# core.net
KiCad netlist of a schematic drawn in EAGLE
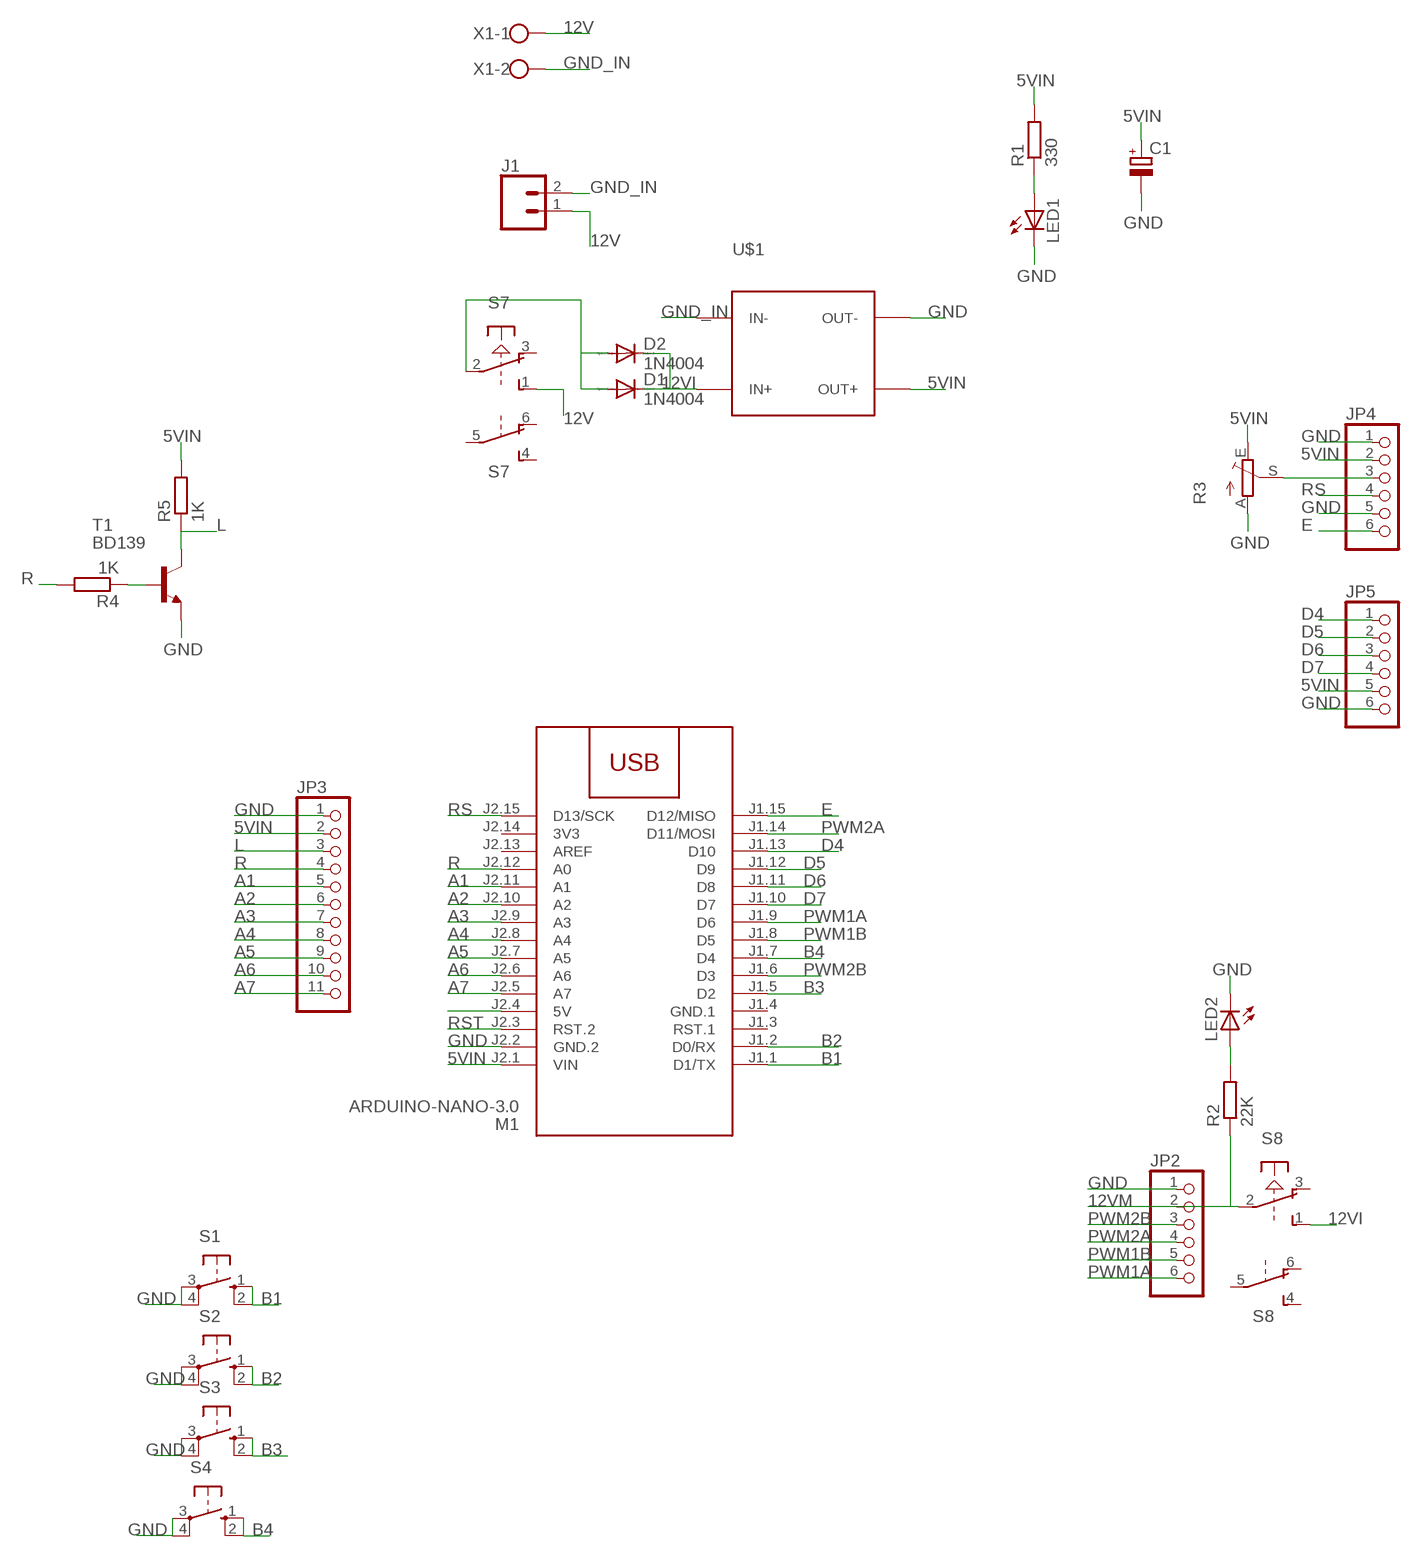
[diagram p0: schematic, sheet 1]

(export (version "E")
  (design (tool "Eeschema 10.0.6"))
  (components
    (comp (ref "C1")
      (value "CPOL-EUE2.5-6")
      (footprint "eagle-import:E2,5-6")
      (libsource (lib "eagle-import") (part "CPOL-EUE2.5-6"))
    )
    (comp (ref "D1")
      (value "1N4004")
      (footprint "eagle-import:DO41-10")
      (libsource (lib "eagle-import") (part "1N4004"))
    )
    (comp (ref "D2")
      (value "1N4004")
      (footprint "eagle-import:DO41-10")
      (libsource (lib "eagle-import") (part "1N4004"))
    )
    (comp (ref "J1")
      (value "CONN_02POLAR")
      (footprint "eagle-import:MOLEX-1X2")
      (libsource (lib "eagle-import") (part "CONN_02POLAR"))
    )
    (comp (ref "JP2")
      (value "PINHD-1X6")
      (footprint "eagle-import:1X06")
      (libsource (lib "eagle-import") (part "PINHD-1X6"))
    )
    (comp (ref "JP3")
      (value "PINHD-1X11")
      (footprint "eagle-import:1X11")
      (libsource (lib "eagle-import") (part "PINHD-1X11"))
    )
    (comp (ref "JP4")
      (value "PINHD-1X6")
      (footprint "eagle-import:1X06")
      (libsource (lib "eagle-import") (part "PINHD-1X6"))
    )
    (comp (ref "JP5")
      (value "PINHD-1X6")
      (footprint "eagle-import:1X06")
      (libsource (lib "eagle-import") (part "PINHD-1X6"))
    )
    (comp (ref "LED1")
      (value "LED3MM")
      (footprint "eagle-import:LED3MM")
      (libsource (lib "eagle-import") (part "LED3MM"))
    )
    (comp (ref "LED2")
      (value "LED3MM")
      (footprint "eagle-import:LED3MM")
      (libsource (lib "eagle-import") (part "LED3MM"))
    )
    (comp (ref "M1")
      (value "ARDUINO-NANO-3.0")
      (footprint "eagle-import:ARDUINO-NANO-3.0")
      (libsource (lib "eagle-import") (part "ARDUINO-NANO-3.0"))
    )
    (comp (ref "R1")
      (value "330")
      (footprint "eagle-import:0207_7")
      (libsource (lib "eagle-import") (part "R-EU_0207/7"))
    )
    (comp (ref "R2")
      (value "22K")
      (footprint "eagle-import:0207_7")
      (libsource (lib "eagle-import") (part "R-EU_0207/7"))
    )
    (comp (ref "R3")
      (value "TRIM_EU-CA6V")
      (footprint "eagle-import:CA6V")
      (libsource (lib "eagle-import") (part "TRIM_EU-CA6V"))
    )
    (comp (ref "R4")
      (value "1K")
      (footprint "eagle-import:0207_7")
      (libsource (lib "eagle-import") (part "R-EU_0207/7"))
    )
    (comp (ref "R5")
      (value "1K")
      (footprint "eagle-import:0207_7")
      (libsource (lib "eagle-import") (part "R-EU_0207/7"))
    )
    (comp (ref "S1")
      (value "10-XX")
      (footprint "eagle-import:B3F-10XX")
      (fields (field (name "MPN") "B3F-1000"))
      (libsource (lib "eagle-import") (part "10-XX"))
    )
    (comp (ref "S2")
      (value "10-XX")
      (footprint "eagle-import:B3F-10XX")
      (fields (field (name "MPN") "B3F-1000"))
      (libsource (lib "eagle-import") (part "10-XX"))
    )
    (comp (ref "S3")
      (value "10-XX")
      (footprint "eagle-import:B3F-10XX")
      (fields (field (name "MPN") "B3F-1000"))
      (libsource (lib "eagle-import") (part "10-XX"))
    )
    (comp (ref "S4")
      (value "10-XX")
      (footprint "eagle-import:B3F-10XX")
      (fields (field (name "MPN") "B3F-1000"))
      (libsource (lib "eagle-import") (part "10-XX"))
    )
    (comp (ref "S7")
      (value "PVA2R")
      (footprint "eagle-import:PVA2R")
      (libsource (lib "eagle-import") (part "PVA2R"))
    )
    (comp (ref "S8")
      (value "PVA2R")
      (footprint "eagle-import:PVA2R")
      (libsource (lib "eagle-import") (part "PVA2R"))
    )
    (comp (ref "T1")
      (value "BD139")
      (footprint "eagle-import:TO126")
      (libsource (lib "eagle-import") (part "BD139"))
    )
    (comp (ref "U$1")
      (value "DC-DC-STEP-DOWN-MP2307")
      (footprint "eagle-import:DC-DC-STEP-DOWN-MP2307")
      (libsource (lib "eagle-import") (part "DC-DC-STEP-DOWN-MP2307"))
    )
    (comp (ref "X1")
      (value "W237-102")
      (footprint "eagle-import:W237-102")
      (fields (field (name "MPN") "237-102"))
      (libsource (lib "eagle-import") (part "W237-102"))
    )
  )
  (nets
    (net (code "1") (name "/3V3") (class "Default")
      (node (ref "M1") (pin "J2.14") (pinfunction "3V3_J2.14") (pintype "power_in"))
    )
    (net (code "2") (name "/5VIN") (class "Default")
      (node (ref "C1") (pin "+") (pinfunction "+_+") (pintype "passive"))
      (node (ref "JP3") (pin "2") (pinfunction "2_2") (pintype "passive"))
      (node (ref "JP4") (pin "2") (pinfunction "2_2") (pintype "passive"))
      (node (ref "JP5") (pin "5") (pinfunction "5_5") (pintype "passive"))
      (node (ref "M1") (pin "J2.1") (pinfunction "VIN_J2.1") (pintype "power_in"))
      (node (ref "R1") (pin "2") (pinfunction "2_2") (pintype "passive"))
      (node (ref "R3") (pin "E") (pinfunction "E_E") (pintype "passive"))
      (node (ref "R5") (pin "2") (pinfunction "2_2") (pintype "passive"))
      (node (ref "U$1") (pin "OUT+") (pinfunction "OUT+_OUT+") (pintype "bidirectional"))
    )
    (net (code "3") (name "/12V") (class "Default")
      (node (ref "J1") (pin "1") (pinfunction "1_1") (pintype "passive"))
      (node (ref "S7") (pin "1") (pinfunction "S_1") (pintype "passive"))
      (node (ref "X1") (pin "1") (pinfunction "KL_1") (pintype "passive"))
    )
    (net (code "4") (name "/12VI") (class "Default")
      (node (ref "D1") (pin "C") (pinfunction "C_C") (pintype "passive"))
      (node (ref "D2") (pin "C") (pinfunction "C_C") (pintype "passive"))
      (node (ref "S8") (pin "1") (pinfunction "S_1") (pintype "passive"))
      (node (ref "U$1") (pin "IN+") (pinfunction "IN+_IN+") (pintype "bidirectional"))
    )
    (net (code "5") (name "/12VM") (class "Default")
      (node (ref "JP2") (pin "2") (pinfunction "2_2") (pintype "passive"))
      (node (ref "R2") (pin "1") (pinfunction "1_1") (pintype "passive"))
      (node (ref "S8") (pin "2") (pinfunction "P_2") (pintype "passive"))
    )
    (net (code "6") (name "/A1") (class "Default")
      (node (ref "JP3") (pin "5") (pinfunction "5_5") (pintype "passive"))
      (node (ref "M1") (pin "J2.11") (pinfunction "A1_J2.11") (pintype "bidirectional"))
    )
    (net (code "7") (name "/A2") (class "Default")
      (node (ref "JP3") (pin "6") (pinfunction "6_6") (pintype "passive"))
      (node (ref "M1") (pin "J2.10") (pinfunction "A2_J2.10") (pintype "bidirectional"))
    )
    (net (code "8") (name "/A3") (class "Default")
      (node (ref "JP3") (pin "7") (pinfunction "7_7") (pintype "passive"))
      (node (ref "M1") (pin "J2.9") (pinfunction "A3_J2.9") (pintype "bidirectional"))
    )
    (net (code "9") (name "/A4") (class "Default")
      (node (ref "JP3") (pin "8") (pinfunction "8_8") (pintype "passive"))
      (node (ref "M1") (pin "J2.8") (pinfunction "A4_J2.8") (pintype "bidirectional"))
    )
    (net (code "10") (name "/A5") (class "Default")
      (node (ref "JP3") (pin "9") (pinfunction "9_9") (pintype "passive"))
      (node (ref "M1") (pin "J2.7") (pinfunction "A5_J2.7") (pintype "bidirectional"))
    )
    (net (code "11") (name "/A6") (class "Default")
      (node (ref "JP3") (pin "10") (pinfunction "10_10") (pintype "passive"))
      (node (ref "M1") (pin "J2.6") (pinfunction "A6_J2.6") (pintype "bidirectional"))
    )
    (net (code "12") (name "/A7") (class "Default")
      (node (ref "JP3") (pin "11") (pinfunction "11_11") (pintype "passive"))
      (node (ref "M1") (pin "J2.5") (pinfunction "A7_J2.5") (pintype "bidirectional"))
    )
    (net (code "13") (name "/B1") (class "Default")
      (node (ref "M1") (pin "J1.1") (pinfunction "D1/TX_J1.1") (pintype "bidirectional"))
      (node (ref "S1") (pin "1") (pinfunction "S_1") (pintype "passive"))
      (node (ref "S1") (pin "2") (pinfunction "S1_2") (pintype "passive"))
    )
    (net (code "14") (name "/B2") (class "Default")
      (node (ref "M1") (pin "J1.2") (pinfunction "D0/RX_J1.2") (pintype "bidirectional"))
      (node (ref "S2") (pin "1") (pinfunction "S_1") (pintype "passive"))
      (node (ref "S2") (pin "2") (pinfunction "S1_2") (pintype "passive"))
    )
    (net (code "15") (name "/B3") (class "Default")
      (node (ref "M1") (pin "J1.5") (pinfunction "D2_J1.5") (pintype "bidirectional"))
      (node (ref "S3") (pin "1") (pinfunction "S_1") (pintype "passive"))
      (node (ref "S3") (pin "2") (pinfunction "S1_2") (pintype "passive"))
    )
    (net (code "16") (name "/B4") (class "Default")
      (node (ref "M1") (pin "J1.7") (pinfunction "D4_J1.7") (pintype "bidirectional"))
      (node (ref "S4") (pin "1") (pinfunction "S_1") (pintype "passive"))
      (node (ref "S4") (pin "2") (pinfunction "S1_2") (pintype "passive"))
    )
    (net (code "17") (name "/D4") (class "Default")
      (node (ref "JP5") (pin "1") (pinfunction "1_1") (pintype "passive"))
      (node (ref "M1") (pin "J1.13") (pinfunction "D10_J1.13") (pintype "bidirectional"))
    )
    (net (code "18") (name "/D5") (class "Default")
      (node (ref "JP5") (pin "2") (pinfunction "2_2") (pintype "passive"))
      (node (ref "M1") (pin "J1.12") (pinfunction "D9_J1.12") (pintype "bidirectional"))
    )
    (net (code "19") (name "/D6") (class "Default")
      (node (ref "JP5") (pin "3") (pinfunction "3_3") (pintype "passive"))
      (node (ref "M1") (pin "J1.11") (pinfunction "D8_J1.11") (pintype "bidirectional"))
    )
    (net (code "20") (name "/D7") (class "Default")
      (node (ref "JP5") (pin "4") (pinfunction "4_4") (pintype "passive"))
      (node (ref "M1") (pin "J1.10") (pinfunction "D7_J1.10") (pintype "bidirectional"))
    )
    (net (code "21") (name "/E") (class "Default")
      (node (ref "JP4") (pin "6") (pinfunction "6_6") (pintype "passive"))
      (node (ref "M1") (pin "J1.15") (pinfunction "D12/MISO_J1.15") (pintype "bidirectional"))
    )
    (net (code "22") (name "/GND") (class "Default")
      (node (ref "C1") (pin "-") (pinfunction "-_-") (pintype "passive"))
      (node (ref "JP2") (pin "1") (pinfunction "1_1") (pintype "passive"))
      (node (ref "JP3") (pin "1") (pinfunction "1_1") (pintype "passive"))
      (node (ref "JP4") (pin "1") (pinfunction "1_1") (pintype "passive"))
      (node (ref "JP4") (pin "5") (pinfunction "5_5") (pintype "passive"))
      (node (ref "JP5") (pin "6") (pinfunction "6_6") (pintype "passive"))
      (node (ref "LED1") (pin "K") (pinfunction "C_K") (pintype "passive"))
      (node (ref "LED2") (pin "K") (pinfunction "C_K") (pintype "passive"))
      (node (ref "M1") (pin "J2.2") (pinfunction "GND.2_J2.2") (pintype "power_in"))
      (node (ref "R3") (pin "A") (pinfunction "A_A") (pintype "passive"))
      (node (ref "S1") (pin "3") (pinfunction "P_3") (pintype "passive"))
      (node (ref "S1") (pin "4") (pinfunction "P1_4") (pintype "passive"))
      (node (ref "S2") (pin "3") (pinfunction "P_3") (pintype "passive"))
      (node (ref "S2") (pin "4") (pinfunction "P1_4") (pintype "passive"))
      (node (ref "S3") (pin "3") (pinfunction "P_3") (pintype "passive"))
      (node (ref "S3") (pin "4") (pinfunction "P1_4") (pintype "passive"))
      (node (ref "S4") (pin "3") (pinfunction "P_3") (pintype "passive"))
      (node (ref "S4") (pin "4") (pinfunction "P1_4") (pintype "passive"))
      (node (ref "T1") (pin "1") (pinfunction "E_1") (pintype "passive"))
      (node (ref "U$1") (pin "OUT-") (pinfunction "OUT-_OUT-") (pintype "bidirectional"))
    )
    (net (code "23") (name "/GND.1") (class "Default")
      (node (ref "M1") (pin "J1.4") (pinfunction "GND.1_J1.4") (pintype "power_in"))
    )
    (net (code "24") (name "/GND_IN") (class "Default")
      (node (ref "J1") (pin "2") (pinfunction "2_2") (pintype "passive"))
      (node (ref "U$1") (pin "IN-") (pinfunction "IN-_IN-") (pintype "bidirectional"))
      (node (ref "X1") (pin "2") (pinfunction "KL_2") (pintype "passive"))
    )
    (net (code "25") (name "/L") (class "Default")
      (node (ref "JP3") (pin "3") (pinfunction "3_3") (pintype "passive"))
      (node (ref "R5") (pin "1") (pinfunction "1_1") (pintype "passive"))
      (node (ref "T1") (pin "2") (pinfunction "C_2") (pintype "passive"))
    )
    (net (code "26") (name "/PWM1A") (class "Default")
      (node (ref "JP2") (pin "6") (pinfunction "6_6") (pintype "passive"))
      (node (ref "M1") (pin "J1.9") (pinfunction "D6_J1.9") (pintype "bidirectional"))
    )
    (net (code "27") (name "/PWM1B") (class "Default")
      (node (ref "JP2") (pin "5") (pinfunction "5_5") (pintype "passive"))
      (node (ref "M1") (pin "J1.8") (pinfunction "D5_J1.8") (pintype "bidirectional"))
    )
    (net (code "28") (name "/PWM2A") (class "Default")
      (node (ref "JP2") (pin "4") (pinfunction "4_4") (pintype "passive"))
      (node (ref "M1") (pin "J1.14") (pinfunction "D11/MOSI_J1.14") (pintype "bidirectional"))
    )
    (net (code "29") (name "/PWM2B") (class "Default")
      (node (ref "JP2") (pin "3") (pinfunction "3_3") (pintype "passive"))
      (node (ref "M1") (pin "J1.6") (pinfunction "D3_J1.6") (pintype "bidirectional"))
    )
    (net (code "30") (name "/R") (class "Default")
      (node (ref "JP3") (pin "4") (pinfunction "4_4") (pintype "passive"))
      (node (ref "M1") (pin "J2.12") (pinfunction "A0_J2.12") (pintype "bidirectional"))
      (node (ref "R4") (pin "2") (pinfunction "2_2") (pintype "passive"))
    )
    (net (code "31") (name "/RS") (class "Default")
      (node (ref "JP4") (pin "4") (pinfunction "4_4") (pintype "passive"))
      (node (ref "M1") (pin "J2.15") (pinfunction "D13/SCK_J2.15") (pintype "bidirectional"))
    )
    (net (code "32") (name "/RST") (class "Default")
      (node (ref "M1") (pin "J2.3") (pinfunction "RST.2_J2.3") (pintype "bidirectional"))
    )
    (net (code "33") (name "Net-(JP4-Pad3)") (class "Default")
      (node (ref "JP4") (pin "3") (pinfunction "3_3") (pintype "passive"))
      (node (ref "R3") (pin "S") (pinfunction "S_S") (pintype "passive"))
    )
    (net (code "34") (name "Net-(LED1-PadA)") (class "Default")
      (node (ref "LED1") (pin "A") (pinfunction "A_A") (pintype "passive"))
      (node (ref "R1") (pin "1") (pinfunction "1_1") (pintype "passive"))
    )
    (net (code "35") (name "Net-(LED2-PadA)") (class "Default")
      (node (ref "LED2") (pin "A") (pinfunction "A_A") (pintype "passive"))
      (node (ref "R2") (pin "2") (pinfunction "2_2") (pintype "passive"))
    )
    (net (code "36") (name "Net-(S7A-P)") (class "Default")
      (node (ref "D1") (pin "A") (pinfunction "A_A") (pintype "passive"))
      (node (ref "D2") (pin "A") (pinfunction "A_A") (pintype "passive"))
      (node (ref "S7") (pin "2") (pinfunction "P_2") (pintype "passive"))
    )
    (net (code "37") (name "Net-(T1-B)") (class "Default")
      (node (ref "R4") (pin "1") (pinfunction "1_1") (pintype "passive"))
      (node (ref "T1") (pin "3") (pinfunction "B_3") (pintype "passive"))
    )
    (net (code "38") (name "unconnected-(M1-5V-PadJ2.4)") (class "Default")
      (node (ref "M1") (pin "J2.4") (pinfunction "5V_J2.4") (pintype "power_in"))
    )
    (net (code "39") (name "unconnected-(M1-AREF-PadJ2.13)") (class "Default")
      (node (ref "M1") (pin "J2.13") (pinfunction "AREF_J2.13") (pintype "bidirectional"))
    )
    (net (code "40") (name "unconnected-(M1-RST.1-PadJ1.3)") (class "Default")
      (node (ref "M1") (pin "J1.3") (pinfunction "RST.1_J1.3") (pintype "bidirectional"))
    )
    (net (code "41") (name "unconnected-(S7A-O-Pad3)") (class "Default")
      (node (ref "S7") (pin "3") (pinfunction "O_3") (pintype "passive"))
    )
    (net (code "42") (name "unconnected-(S7B-O-Pad6)") (class "Default")
      (node (ref "S7") (pin "6") (pinfunction "O_6") (pintype "passive"))
    )
    (net (code "43") (name "unconnected-(S7B-P-Pad5)") (class "Default")
      (node (ref "S7") (pin "5") (pinfunction "P_5") (pintype "passive"))
    )
    (net (code "44") (name "unconnected-(S7B-S-Pad4)") (class "Default")
      (node (ref "S7") (pin "4") (pinfunction "S_4") (pintype "passive"))
    )
    (net (code "45") (name "unconnected-(S8A-O-Pad3)") (class "Default")
      (node (ref "S8") (pin "3") (pinfunction "O_3") (pintype "passive"))
    )
    (net (code "46") (name "unconnected-(S8B-O-Pad6)") (class "Default")
      (node (ref "S8") (pin "6") (pinfunction "O_6") (pintype "passive"))
    )
    (net (code "47") (name "unconnected-(S8B-P-Pad5)") (class "Default")
      (node (ref "S8") (pin "5") (pinfunction "P_5") (pintype "passive"))
    )
    (net (code "48") (name "unconnected-(S8B-S-Pad4)") (class "Default")
      (node (ref "S8") (pin "4") (pinfunction "S_4") (pintype "passive"))
    )
  )
)
